# Sitara_DDR.net
KiCad netlist of a schematic drawn in Altium Designer
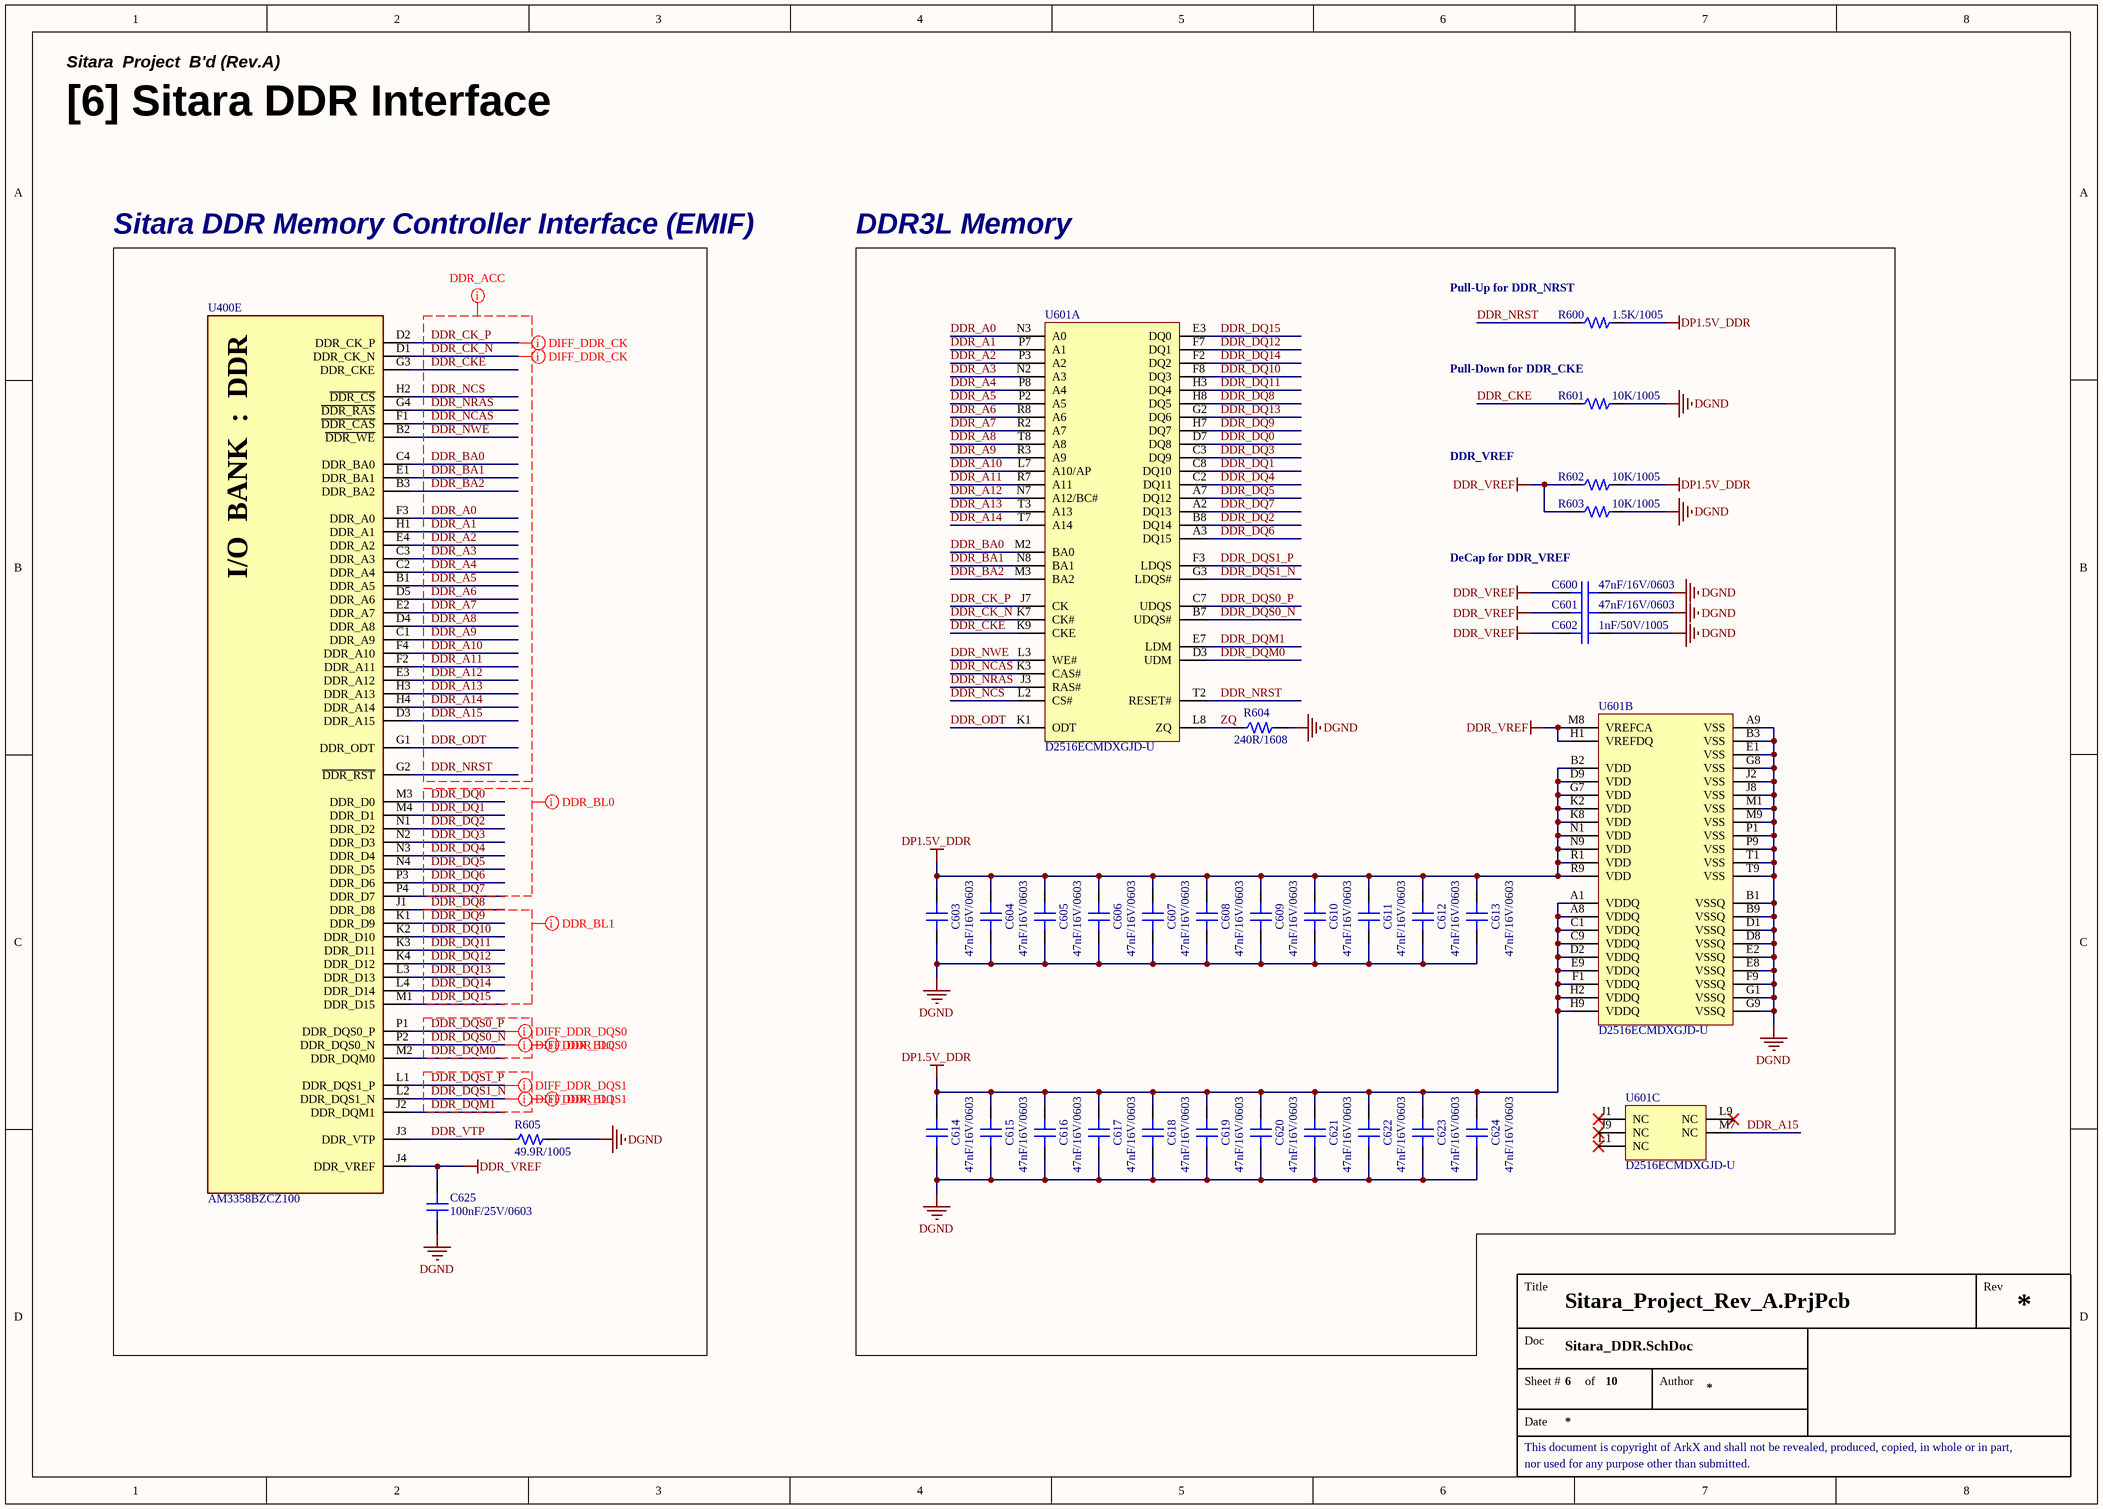
[diagram p0: Sitara_DDR.SchDoc]

(export (version "E")
  (design (tool "Eeschema 10.0.6"))
  (components
    (comp (ref "C600")
      (value "47nF/16V/0603")
      (footprint "CAP 0603 (0201_INCH)")
      (description "16V 47nF X5R ±10% 0201 Multilayer Ceramic Capacitors MLCC - SMD/SMT ROHS")
      (fields (field (name "LCSC PART #") "C88917"))
      (libsource (lib "Arkx") (part "CAP_47nF/16V/0603"))
    )
    (comp (ref "C601")
      (value "47nF/16V/0603")
      (footprint "CAP 0603 (0201_INCH)")
      (description "16V 47nF X5R ±10% 0201 Multilayer Ceramic Capacitors MLCC - SMD/SMT ROHS")
      (fields (field (name "LCSC PART #") "C88917"))
      (libsource (lib "Arkx") (part "CAP_47nF/16V/0603"))
    )
    (comp (ref "C602")
      (value "1nF/50V/1005")
      (footprint "CAP 1005 (0402_INCH)")
      (description "Ceramic CAP_1nF/50V/1005")
      (fields (field (name "LCSC PART #") "C1523"))
      (libsource (lib "Arkx") (part "CAP_1nF/50V/1005"))
    )
    (comp (ref "C603")
      (value "47nF/16V/0603")
      (footprint "CAP 0603 (0201_INCH)")
      (description "16V 47nF X5R ±10% 0201 Multilayer Ceramic Capacitors MLCC - SMD/SMT ROHS")
      (fields (field (name "LCSC PART #") "C88917"))
      (libsource (lib "Arkx") (part "CAP_47nF/16V/0603"))
    )
    (comp (ref "C604")
      (value "47nF/16V/0603")
      (footprint "CAP 0603 (0201_INCH)")
      (description "16V 47nF X5R ±10% 0201 Multilayer Ceramic Capacitors MLCC - SMD/SMT ROHS")
      (fields (field (name "LCSC PART #") "C88917"))
      (libsource (lib "Arkx") (part "CAP_47nF/16V/0603"))
    )
    (comp (ref "C605")
      (value "47nF/16V/0603")
      (footprint "CAP 0603 (0201_INCH)")
      (description "16V 47nF X5R ±10% 0201 Multilayer Ceramic Capacitors MLCC - SMD/SMT ROHS")
      (fields (field (name "LCSC PART #") "C88917"))
      (libsource (lib "Arkx") (part "CAP_47nF/16V/0603"))
    )
    (comp (ref "C606")
      (value "47nF/16V/0603")
      (footprint "CAP 0603 (0201_INCH)")
      (description "16V 47nF X5R ±10% 0201 Multilayer Ceramic Capacitors MLCC - SMD/SMT ROHS")
      (fields (field (name "LCSC PART #") "C88917"))
      (libsource (lib "Arkx") (part "CAP_47nF/16V/0603"))
    )
    (comp (ref "C607")
      (value "47nF/16V/0603")
      (footprint "CAP 0603 (0201_INCH)")
      (description "16V 47nF X5R ±10% 0201 Multilayer Ceramic Capacitors MLCC - SMD/SMT ROHS")
      (fields (field (name "LCSC PART #") "C88917"))
      (libsource (lib "Arkx") (part "CAP_47nF/16V/0603"))
    )
    (comp (ref "C608")
      (value "47nF/16V/0603")
      (footprint "CAP 0603 (0201_INCH)")
      (description "16V 47nF X5R ±10% 0201 Multilayer Ceramic Capacitors MLCC - SMD/SMT ROHS")
      (fields (field (name "LCSC PART #") "C88917"))
      (libsource (lib "Arkx") (part "CAP_47nF/16V/0603"))
    )
    (comp (ref "C609")
      (value "47nF/16V/0603")
      (footprint "CAP 0603 (0201_INCH)")
      (description "16V 47nF X5R ±10% 0201 Multilayer Ceramic Capacitors MLCC - SMD/SMT ROHS")
      (fields (field (name "LCSC PART #") "C88917"))
      (libsource (lib "Arkx") (part "CAP_47nF/16V/0603"))
    )
    (comp (ref "C610")
      (value "47nF/16V/0603")
      (footprint "CAP 0603 (0201_INCH)")
      (description "16V 47nF X5R ±10% 0201 Multilayer Ceramic Capacitors MLCC - SMD/SMT ROHS")
      (fields (field (name "LCSC PART #") "C88917"))
      (libsource (lib "Arkx") (part "CAP_47nF/16V/0603"))
    )
    (comp (ref "C611")
      (value "47nF/16V/0603")
      (footprint "CAP 0603 (0201_INCH)")
      (description "16V 47nF X5R ±10% 0201 Multilayer Ceramic Capacitors MLCC - SMD/SMT ROHS")
      (fields (field (name "LCSC PART #") "C88917"))
      (libsource (lib "Arkx") (part "CAP_47nF/16V/0603"))
    )
    (comp (ref "C612")
      (value "47nF/16V/0603")
      (footprint "CAP 0603 (0201_INCH)")
      (description "16V 47nF X5R ±10% 0201 Multilayer Ceramic Capacitors MLCC - SMD/SMT ROHS")
      (fields (field (name "LCSC PART #") "C88917"))
      (libsource (lib "Arkx") (part "CAP_47nF/16V/0603"))
    )
    (comp (ref "C613")
      (value "47nF/16V/0603")
      (footprint "CAP 0603 (0201_INCH)")
      (description "16V 47nF X5R ±10% 0201 Multilayer Ceramic Capacitors MLCC - SMD/SMT ROHS")
      (fields (field (name "LCSC PART #") "C88917"))
      (libsource (lib "Arkx") (part "CAP_47nF/16V/0603"))
    )
    (comp (ref "C614")
      (value "47nF/16V/0603")
      (footprint "CAP 0603 (0201_INCH)")
      (description "16V 47nF X5R ±10% 0201 Multilayer Ceramic Capacitors MLCC - SMD/SMT ROHS")
      (fields (field (name "LCSC PART #") "C88917"))
      (libsource (lib "Arkx") (part "CAP_47nF/16V/0603"))
    )
    (comp (ref "C615")
      (value "47nF/16V/0603")
      (footprint "CAP 0603 (0201_INCH)")
      (description "16V 47nF X5R ±10% 0201 Multilayer Ceramic Capacitors MLCC - SMD/SMT ROHS")
      (fields (field (name "LCSC PART #") "C88917"))
      (libsource (lib "Arkx") (part "CAP_47nF/16V/0603"))
    )
    (comp (ref "C616")
      (value "47nF/16V/0603")
      (footprint "CAP 0603 (0201_INCH)")
      (description "16V 47nF X5R ±10% 0201 Multilayer Ceramic Capacitors MLCC - SMD/SMT ROHS")
      (fields (field (name "LCSC PART #") "C88917"))
      (libsource (lib "Arkx") (part "CAP_47nF/16V/0603"))
    )
    (comp (ref "C617")
      (value "47nF/16V/0603")
      (footprint "CAP 0603 (0201_INCH)")
      (description "16V 47nF X5R ±10% 0201 Multilayer Ceramic Capacitors MLCC - SMD/SMT ROHS")
      (fields (field (name "LCSC PART #") "C88917"))
      (libsource (lib "Arkx") (part "CAP_47nF/16V/0603"))
    )
    (comp (ref "C618")
      (value "47nF/16V/0603")
      (footprint "CAP 0603 (0201_INCH)")
      (description "16V 47nF X5R ±10% 0201 Multilayer Ceramic Capacitors MLCC - SMD/SMT ROHS")
      (fields (field (name "LCSC PART #") "C88917"))
      (libsource (lib "Arkx") (part "CAP_47nF/16V/0603"))
    )
    (comp (ref "C619")
      (value "47nF/16V/0603")
      (footprint "CAP 0603 (0201_INCH)")
      (description "16V 47nF X5R ±10% 0201 Multilayer Ceramic Capacitors MLCC - SMD/SMT ROHS")
      (fields (field (name "LCSC PART #") "C88917"))
      (libsource (lib "Arkx") (part "CAP_47nF/16V/0603"))
    )
    (comp (ref "C620")
      (value "47nF/16V/0603")
      (footprint "CAP 0603 (0201_INCH)")
      (description "16V 47nF X5R ±10% 0201 Multilayer Ceramic Capacitors MLCC - SMD/SMT ROHS")
      (fields (field (name "LCSC PART #") "C88917"))
      (libsource (lib "Arkx") (part "CAP_47nF/16V/0603"))
    )
    (comp (ref "C621")
      (value "47nF/16V/0603")
      (footprint "CAP 0603 (0201_INCH)")
      (description "16V 47nF X5R ±10% 0201 Multilayer Ceramic Capacitors MLCC - SMD/SMT ROHS")
      (fields (field (name "LCSC PART #") "C88917"))
      (libsource (lib "Arkx") (part "CAP_47nF/16V/0603"))
    )
    (comp (ref "C622")
      (value "47nF/16V/0603")
      (footprint "CAP 0603 (0201_INCH)")
      (description "16V 47nF X5R ±10% 0201 Multilayer Ceramic Capacitors MLCC - SMD/SMT ROHS")
      (fields (field (name "LCSC PART #") "C88917"))
      (libsource (lib "Arkx") (part "CAP_47nF/16V/0603"))
    )
    (comp (ref "C623")
      (value "47nF/16V/0603")
      (footprint "CAP 0603 (0201_INCH)")
      (description "16V 47nF X5R ±10% 0201 Multilayer Ceramic Capacitors MLCC - SMD/SMT ROHS")
      (fields (field (name "LCSC PART #") "C88917"))
      (libsource (lib "Arkx") (part "CAP_47nF/16V/0603"))
    )
    (comp (ref "C624")
      (value "47nF/16V/0603")
      (footprint "CAP 0603 (0201_INCH)")
      (description "16V 47nF X5R ±10% 0201 Multilayer Ceramic Capacitors MLCC - SMD/SMT ROHS")
      (fields (field (name "LCSC PART #") "C88917"))
      (libsource (lib "Arkx") (part "CAP_47nF/16V/0603"))
    )
    (comp (ref "C625")
      (value "100nF/25V/0603")
      (footprint "CAP 0603 (0201_INCH)")
      (description "Ceramic CAP_100nF/25V/0603")
      (fields (field (name "LCSC PART #") "C181047"))
      (libsource (lib "Arkx") (part "CAP_100nF/25V/0603"))
    )
    (comp (ref "R600")
      (value "1.5K/1005")
      (footprint "RES 1005 (0402_inch)")
      (description "RES_1.5K/1005/62.5mW")
      (fields (field (name "LCSC PART #") "C25867"))
      (libsource (lib "Arkx") (part "RES_1.5K/1005/62.5mW"))
    )
    (comp (ref "R601")
      (value "10K/1005")
      (footprint "RES 1005 (0402_inch)")
      (description "RES_10K/1005/62.5mW")
      (fields (field (name "LCSC PART #") "C25744"))
      (libsource (lib "Arkx") (part "RES_10K/1005/62.5mW"))
    )
    (comp (ref "R602")
      (value "10K/1005")
      (footprint "RES 1005 (0402_inch)")
      (description "RES_10K/1005/62.5mW")
      (fields (field (name "LCSC PART #") "C25744"))
      (libsource (lib "Arkx") (part "RES_10K/1005/62.5mW"))
    )
    (comp (ref "R603")
      (value "10K/1005")
      (footprint "RES 1005 (0402_inch)")
      (description "RES_10K/1005/62.5mW")
      (fields (field (name "LCSC PART #") "C25744"))
      (libsource (lib "Arkx") (part "RES_10K/1005/62.5mW"))
    )
    (comp (ref "R604")
      (value "240R/1608")
      (footprint "RES 1608 (0603_inch)")
      (description "RES_240R/1608/0.1W")
      (fields (field (name "LCSC PART #") "C23350"))
      (libsource (lib "Arkx") (part "RES_240R/1608/0.1W"))
    )
    (comp (ref "R605")
      (value "49.9R/1005")
      (footprint "RES 1005 (0402_inch)")
      (description "RES_49.9R/1005/62.5mW")
      (fields (field (name "LCSC PART #") "C25120"))
      (libsource (lib "Arkx") (part "RES_49.9R/1005/62.5mW"))
    )
    (comp (ref "U400")
      (value "AM3358BZCZ100")
      (footprint "IC_SOC_AM3358BZCZ100")
      (description "ARM® Cortex®-A8 Microprocessor IC Sitara™ 1 Core, 32-Bit 1.0GHz 324-NFBGA (15x15)")
      (fields (field (name "LCSC PART #") "C73932"))
      (libsource (lib "Arkx") (part "IC_SOC_AM3358BZCZ100"))
    )
    (comp (ref "U601")
      (value "D2516ECMDXGJD-U")
      (footprint "IC_MEM_DDR3L_MT41K256M16TW-107 IT:P")
      (description "DRAM 4Gb 96 ball FBGA DDR3L 1866")
      (fields (field (name "LCSC PART #") "C2927180"))
      (libsource (lib "Arkx") (part "IC_MEM_DDR3L_D2516ECMDXGJD-U"))
    )
  )
  (nets
    (net (code "1") (name "/DDR_A0") (class "Default")
      (node (ref "U400") (pin "F3") (pinfunction "DDR_A0_F3") (pintype "passive"))
      (node (ref "U601") (pin "N3") (pinfunction "A0_N3") (pintype "passive"))
    )
    (net (code "2") (name "/DDR_A1") (class "Default")
      (node (ref "U400") (pin "H1") (pinfunction "DDR_A1_H1") (pintype "passive"))
      (node (ref "U601") (pin "P7") (pinfunction "A1_P7") (pintype "passive"))
    )
    (net (code "3") (name "/DDR_A2") (class "Default")
      (node (ref "U400") (pin "E4") (pinfunction "DDR_A2_E4") (pintype "passive"))
      (node (ref "U601") (pin "P3") (pinfunction "A2_P3") (pintype "passive"))
    )
    (net (code "4") (name "/DDR_A3") (class "Default")
      (node (ref "U400") (pin "C3") (pinfunction "DDR_A3_C3") (pintype "passive"))
      (node (ref "U601") (pin "N2") (pinfunction "A3_N2") (pintype "passive"))
    )
    (net (code "5") (name "/DDR_A4") (class "Default")
      (node (ref "U400") (pin "C2") (pinfunction "DDR_A4_C2") (pintype "passive"))
      (node (ref "U601") (pin "P8") (pinfunction "A4_P8") (pintype "passive"))
    )
    (net (code "6") (name "/DDR_A5") (class "Default")
      (node (ref "U400") (pin "B1") (pinfunction "DDR_A5_B1") (pintype "passive"))
      (node (ref "U601") (pin "P2") (pinfunction "A5_P2") (pintype "passive"))
    )
    (net (code "7") (name "/DDR_A6") (class "Default")
      (node (ref "U400") (pin "D5") (pinfunction "DDR_A6_D5") (pintype "passive"))
      (node (ref "U601") (pin "R8") (pinfunction "A6_R8") (pintype "passive"))
    )
    (net (code "8") (name "/DDR_A7") (class "Default")
      (node (ref "U400") (pin "E2") (pinfunction "DDR_A7_E2") (pintype "passive"))
      (node (ref "U601") (pin "R2") (pinfunction "A7_R2") (pintype "passive"))
    )
    (net (code "9") (name "/DDR_A8") (class "Default")
      (node (ref "U400") (pin "D4") (pinfunction "DDR_A8_D4") (pintype "passive"))
      (node (ref "U601") (pin "T8") (pinfunction "A8_T8") (pintype "passive"))
    )
    (net (code "10") (name "/DDR_A9") (class "Default")
      (node (ref "U400") (pin "C1") (pinfunction "DDR_A9_C1") (pintype "passive"))
      (node (ref "U601") (pin "R3") (pinfunction "A9_R3") (pintype "passive"))
    )
    (net (code "11") (name "/DDR_A10") (class "Default")
      (node (ref "U400") (pin "F4") (pinfunction "DDR_A10_F4") (pintype "passive"))
      (node (ref "U601") (pin "L7") (pinfunction "A10/AP_L7") (pintype "passive"))
    )
    (net (code "12") (name "/DDR_A11") (class "Default")
      (node (ref "U400") (pin "F2") (pinfunction "DDR_A11_F2") (pintype "passive"))
      (node (ref "U601") (pin "R7") (pinfunction "A11_R7") (pintype "passive"))
    )
    (net (code "13") (name "/DDR_A12") (class "Default")
      (node (ref "U400") (pin "E3") (pinfunction "DDR_A12_E3") (pintype "passive"))
      (node (ref "U601") (pin "N7") (pinfunction "A12/BC#_N7") (pintype "passive"))
    )
    (net (code "14") (name "/DDR_A13") (class "Default")
      (node (ref "U400") (pin "H3") (pinfunction "DDR_A13_H3") (pintype "passive"))
      (node (ref "U601") (pin "T3") (pinfunction "A13_T3") (pintype "passive"))
    )
    (net (code "15") (name "/DDR_A14") (class "Default")
      (node (ref "U400") (pin "H4") (pinfunction "DDR_A14_H4") (pintype "passive"))
      (node (ref "U601") (pin "T7") (pinfunction "A14_T7") (pintype "passive"))
    )
    (net (code "16") (name "/DDR_A15") (class "Default")
      (node (ref "U400") (pin "D3") (pinfunction "DDR_A15_D3") (pintype "passive"))
      (node (ref "U601") (pin "M7") (pinfunction "NC_M7") (pintype "passive"))
    )
    (net (code "17") (name "/DDR_BA0") (class "Default")
      (node (ref "U400") (pin "C4") (pinfunction "DDR_BA0_C4") (pintype "passive"))
      (node (ref "U601") (pin "M2") (pinfunction "BA0_M2") (pintype "passive"))
    )
    (net (code "18") (name "/DDR_BA1") (class "Default")
      (node (ref "U400") (pin "E1") (pinfunction "DDR_BA1_E1") (pintype "passive"))
      (node (ref "U601") (pin "N8") (pinfunction "BA1_N8") (pintype "passive"))
    )
    (net (code "19") (name "/DDR_BA2") (class "Default")
      (node (ref "U400") (pin "B3") (pinfunction "DDR_BA2_B3") (pintype "passive"))
      (node (ref "U601") (pin "M3") (pinfunction "BA2_M3") (pintype "passive"))
    )
    (net (code "20") (name "/DDR_CKE") (class "Default")
      (node (ref "R601") (pin "1") (pinfunction "1_1") (pintype "passive"))
      (node (ref "U400") (pin "G3") (pinfunction "DDR_CKE_G3") (pintype "passive"))
      (node (ref "U601") (pin "K9") (pinfunction "CKE_K9") (pintype "passive"))
    )
    (net (code "21") (name "/DDR_CK_N") (class "Default")
      (node (ref "U400") (pin "D1") (pinfunction "DDR_CK_N_D1") (pintype "passive"))
      (node (ref "U601") (pin "K7") (pinfunction "CK#_K7") (pintype "passive"))
    )
    (net (code "22") (name "/DDR_CK_P") (class "Default")
      (node (ref "U400") (pin "D2") (pinfunction "DDR_CK_P_D2") (pintype "passive"))
      (node (ref "U601") (pin "J7") (pinfunction "CK_J7") (pintype "passive"))
    )
    (net (code "23") (name "/DDR_DQ0") (class "Default")
      (node (ref "U400") (pin "M3") (pinfunction "DDR_D0_M3") (pintype "passive"))
      (node (ref "U601") (pin "D7") (pinfunction "DQ8_D7") (pintype "passive"))
    )
    (net (code "24") (name "/DDR_DQ1") (class "Default")
      (node (ref "U400") (pin "M4") (pinfunction "DDR_D1_M4") (pintype "passive"))
      (node (ref "U601") (pin "C8") (pinfunction "DQ10_C8") (pintype "passive"))
    )
    (net (code "25") (name "/DDR_DQ2") (class "Default")
      (node (ref "U400") (pin "N1") (pinfunction "DDR_D2_N1") (pintype "passive"))
      (node (ref "U601") (pin "B8") (pinfunction "DQ14_B8") (pintype "passive"))
    )
    (net (code "26") (name "/DDR_DQ3") (class "Default")
      (node (ref "U400") (pin "N2") (pinfunction "DDR_D3_N2") (pintype "passive"))
      (node (ref "U601") (pin "C3") (pinfunction "DQ9_C3") (pintype "passive"))
    )
    (net (code "27") (name "/DDR_DQ4") (class "Default")
      (node (ref "U400") (pin "N3") (pinfunction "DDR_D4_N3") (pintype "passive"))
      (node (ref "U601") (pin "C2") (pinfunction "DQ11_C2") (pintype "passive"))
    )
    (net (code "28") (name "/DDR_DQ5") (class "Default")
      (node (ref "U400") (pin "N4") (pinfunction "DDR_D5_N4") (pintype "passive"))
      (node (ref "U601") (pin "A7") (pinfunction "DQ12_A7") (pintype "passive"))
    )
    (net (code "29") (name "/DDR_DQ6") (class "Default")
      (node (ref "U400") (pin "P3") (pinfunction "DDR_D6_P3") (pintype "passive"))
      (node (ref "U601") (pin "A3") (pinfunction "DQ15_A3") (pintype "passive"))
    )
    (net (code "30") (name "/DDR_DQ7") (class "Default")
      (node (ref "U400") (pin "P4") (pinfunction "DDR_D7_P4") (pintype "passive"))
      (node (ref "U601") (pin "A2") (pinfunction "DQ13_A2") (pintype "passive"))
    )
    (net (code "31") (name "/DDR_DQ8") (class "Default")
      (node (ref "U400") (pin "J1") (pinfunction "DDR_D8_J1") (pintype "passive"))
      (node (ref "U601") (pin "H8") (pinfunction "DQ5_H8") (pintype "passive"))
    )
    (net (code "32") (name "/DDR_DQ9") (class "Default")
      (node (ref "U400") (pin "K1") (pinfunction "DDR_D9_K1") (pintype "passive"))
      (node (ref "U601") (pin "H7") (pinfunction "DQ7_H7") (pintype "passive"))
    )
    (net (code "33") (name "/DDR_DQ10") (class "Default")
      (node (ref "U400") (pin "K2") (pinfunction "DDR_D10_K2") (pintype "passive"))
      (node (ref "U601") (pin "F8") (pinfunction "DQ3_F8") (pintype "passive"))
    )
    (net (code "34") (name "/DDR_DQ11") (class "Default")
      (node (ref "U400") (pin "K3") (pinfunction "DDR_D11_K3") (pintype "passive"))
      (node (ref "U601") (pin "H3") (pinfunction "DQ4_H3") (pintype "passive"))
    )
    (net (code "35") (name "/DDR_DQ12") (class "Default")
      (node (ref "U400") (pin "K4") (pinfunction "DDR_D12_K4") (pintype "passive"))
      (node (ref "U601") (pin "F7") (pinfunction "DQ1_F7") (pintype "passive"))
    )
    (net (code "36") (name "/DDR_DQ13") (class "Default")
      (node (ref "U400") (pin "L3") (pinfunction "DDR_D13_L3") (pintype "passive"))
      (node (ref "U601") (pin "G2") (pinfunction "DQ6_G2") (pintype "passive"))
    )
    (net (code "37") (name "/DDR_DQ14") (class "Default")
      (node (ref "U400") (pin "L4") (pinfunction "DDR_D14_L4") (pintype "passive"))
      (node (ref "U601") (pin "F2") (pinfunction "DQ2_F2") (pintype "passive"))
    )
    (net (code "38") (name "/DDR_DQ15") (class "Default")
      (node (ref "U400") (pin "M1") (pinfunction "DDR_D15_M1") (pintype "passive"))
      (node (ref "U601") (pin "E3") (pinfunction "DQ0_E3") (pintype "passive"))
    )
    (net (code "39") (name "/DDR_DQM0") (class "Default")
      (node (ref "U400") (pin "M2") (pinfunction "DDR_DQM0_M2") (pintype "passive"))
      (node (ref "U601") (pin "D3") (pinfunction "UDM_D3") (pintype "passive"))
    )
    (net (code "40") (name "/DDR_DQM1") (class "Default")
      (node (ref "U400") (pin "J2") (pinfunction "DDR_DQM1_J2") (pintype "passive"))
      (node (ref "U601") (pin "E7") (pinfunction "LDM_E7") (pintype "passive"))
    )
    (net (code "41") (name "/DDR_DQS0_N") (class "Default")
      (node (ref "U400") (pin "P2") (pinfunction "DDR_DQS0_N_P2") (pintype "passive"))
      (node (ref "U601") (pin "B7") (pinfunction "UDQS#_B7") (pintype "passive"))
    )
    (net (code "42") (name "/DDR_DQS0_P") (class "Default")
      (node (ref "U400") (pin "P1") (pinfunction "DDR_DQS0_P_P1") (pintype "passive"))
      (node (ref "U601") (pin "C7") (pinfunction "UDQS_C7") (pintype "passive"))
    )
    (net (code "43") (name "/DDR_DQS1_N") (class "Default")
      (node (ref "U400") (pin "L2") (pinfunction "DDR_DQS1_N_L2") (pintype "passive"))
      (node (ref "U601") (pin "G3") (pinfunction "LDQS#_G3") (pintype "passive"))
    )
    (net (code "44") (name "/DDR_DQS1_P") (class "Default")
      (node (ref "U400") (pin "L1") (pinfunction "DDR_DQS1_P_L1") (pintype "passive"))
      (node (ref "U601") (pin "F3") (pinfunction "LDQS_F3") (pintype "passive"))
    )
    (net (code "45") (name "/DDR_NCAS") (class "Default")
      (node (ref "U400") (pin "F1") (pinfunction "~{DDR_CAS}_F1") (pintype "passive"))
      (node (ref "U601") (pin "K3") (pinfunction "CAS#_K3") (pintype "passive"))
    )
    (net (code "46") (name "/DDR_NCS") (class "Default")
      (node (ref "U400") (pin "H2") (pinfunction "~{DDR_CS}_H2") (pintype "passive"))
      (node (ref "U601") (pin "L2") (pinfunction "CS#_L2") (pintype "passive"))
    )
    (net (code "47") (name "/DDR_NRAS") (class "Default")
      (node (ref "U400") (pin "G4") (pinfunction "~{DDR_RAS}_G4") (pintype "passive"))
      (node (ref "U601") (pin "J3") (pinfunction "RAS#_J3") (pintype "passive"))
    )
    (net (code "48") (name "/DDR_NRST") (class "Default")
      (node (ref "R600") (pin "1") (pinfunction "1_1") (pintype "passive"))
      (node (ref "U400") (pin "G2") (pinfunction "~{DDR_RST}_G2") (pintype "passive"))
      (node (ref "U601") (pin "T2") (pinfunction "RESET#_T2") (pintype "passive"))
    )
    (net (code "49") (name "/DDR_NWE") (class "Default")
      (node (ref "U400") (pin "B2") (pinfunction "~{DDR_WE}_B2") (pintype "passive"))
      (node (ref "U601") (pin "L3") (pinfunction "WE#_L3") (pintype "passive"))
    )
    (net (code "50") (name "/DDR_ODT") (class "Default")
      (node (ref "U400") (pin "G1") (pinfunction "DDR_ODT_G1") (pintype "passive"))
      (node (ref "U601") (pin "K1") (pinfunction "ODT_K1") (pintype "passive"))
    )
    (net (code "51") (name "/DDR_VTP") (class "Default")
      (node (ref "R605") (pin "1") (pinfunction "1_1") (pintype "passive"))
      (node (ref "U400") (pin "J3") (pinfunction "DDR_VTP_J3") (pintype "passive"))
    )
    (net (code "52") (name "/ZQ") (class "Default")
      (node (ref "R604") (pin "1") (pinfunction "1_1") (pintype "passive"))
      (node (ref "U601") (pin "L8") (pinfunction "ZQ_L8") (pintype "passive"))
    )
    (net (code "53") (name "DDR_VREF") (class "Default")
      (node (ref "C600") (pin "1") (pinfunction "1_1") (pintype "passive"))
      (node (ref "C601") (pin "1") (pinfunction "1_1") (pintype "passive"))
      (node (ref "C602") (pin "1") (pinfunction "1_1") (pintype "passive"))
      (node (ref "C625") (pin "2") (pinfunction "2_2") (pintype "passive"))
      (node (ref "R602") (pin "1") (pinfunction "1_1") (pintype "passive"))
      (node (ref "R603") (pin "1") (pinfunction "1_1") (pintype "passive"))
      (node (ref "U400") (pin "J4") (pinfunction "DDR_VREF_J4") (pintype "passive"))
      (node (ref "U601") (pin "H1") (pinfunction "VREFDQ_H1") (pintype "passive"))
      (node (ref "U601") (pin "M8") (pinfunction "VREFCA_M8") (pintype "passive"))
    )
    (net (code "54") (name "DGND") (class "Default")
      (node (ref "C600") (pin "2") (pinfunction "2_2") (pintype "passive"))
      (node (ref "C601") (pin "2") (pinfunction "2_2") (pintype "passive"))
      (node (ref "C602") (pin "2") (pinfunction "2_2") (pintype "passive"))
      (node (ref "C603") (pin "1") (pinfunction "1_1") (pintype "passive"))
      (node (ref "C604") (pin "1") (pinfunction "1_1") (pintype "passive"))
      (node (ref "C605") (pin "1") (pinfunction "1_1") (pintype "passive"))
      (node (ref "C606") (pin "1") (pinfunction "1_1") (pintype "passive"))
      (node (ref "C607") (pin "1") (pinfunction "1_1") (pintype "passive"))
      (node (ref "C608") (pin "1") (pinfunction "1_1") (pintype "passive"))
      (node (ref "C609") (pin "1") (pinfunction "1_1") (pintype "passive"))
      (node (ref "C610") (pin "1") (pinfunction "1_1") (pintype "passive"))
      (node (ref "C611") (pin "1") (pinfunction "1_1") (pintype "passive"))
      (node (ref "C612") (pin "1") (pinfunction "1_1") (pintype "passive"))
      (node (ref "C613") (pin "1") (pinfunction "1_1") (pintype "passive"))
      (node (ref "C614") (pin "1") (pinfunction "1_1") (pintype "passive"))
      (node (ref "C615") (pin "1") (pinfunction "1_1") (pintype "passive"))
      (node (ref "C616") (pin "1") (pinfunction "1_1") (pintype "passive"))
      (node (ref "C617") (pin "1") (pinfunction "1_1") (pintype "passive"))
      (node (ref "C618") (pin "1") (pinfunction "1_1") (pintype "passive"))
      (node (ref "C619") (pin "1") (pinfunction "1_1") (pintype "passive"))
      (node (ref "C620") (pin "1") (pinfunction "1_1") (pintype "passive"))
      (node (ref "C621") (pin "1") (pinfunction "1_1") (pintype "passive"))
      (node (ref "C622") (pin "1") (pinfunction "1_1") (pintype "passive"))
      (node (ref "C623") (pin "1") (pinfunction "1_1") (pintype "passive"))
      (node (ref "C624") (pin "1") (pinfunction "1_1") (pintype "passive"))
      (node (ref "C625") (pin "1") (pinfunction "1_1") (pintype "passive"))
      (node (ref "R601") (pin "2") (pinfunction "2_2") (pintype "passive"))
      (node (ref "R603") (pin "2") (pinfunction "2_2") (pintype "passive"))
      (node (ref "R604") (pin "2") (pinfunction "2_2") (pintype "passive"))
      (node (ref "R605") (pin "2") (pinfunction "2_2") (pintype "passive"))
      (node (ref "U601") (pin "A9") (pinfunction "VSS_A9") (pintype "passive"))
      (node (ref "U601") (pin "B1") (pinfunction "VSSQ_B1") (pintype "passive"))
      (node (ref "U601") (pin "B3") (pinfunction "VSS_B3") (pintype "passive"))
      (node (ref "U601") (pin "B9") (pinfunction "VSSQ_B9") (pintype "passive"))
      (node (ref "U601") (pin "D1") (pinfunction "VSSQ_D1") (pintype "passive"))
      (node (ref "U601") (pin "D8") (pinfunction "VSSQ_D8") (pintype "passive"))
      (node (ref "U601") (pin "E1") (pinfunction "VSS_E1") (pintype "passive"))
      (node (ref "U601") (pin "E2") (pinfunction "VSSQ_E2") (pintype "passive"))
      (node (ref "U601") (pin "E8") (pinfunction "VSSQ_E8") (pintype "passive"))
      (node (ref "U601") (pin "F9") (pinfunction "VSSQ_F9") (pintype "passive"))
      (node (ref "U601") (pin "G1") (pinfunction "VSSQ_G1") (pintype "passive"))
      (node (ref "U601") (pin "G8") (pinfunction "VSS_G8") (pintype "passive"))
      (node (ref "U601") (pin "G9") (pinfunction "VSSQ_G9") (pintype "passive"))
      (node (ref "U601") (pin "J2") (pinfunction "VSS_J2") (pintype "passive"))
      (node (ref "U601") (pin "J8") (pinfunction "VSS_J8") (pintype "passive"))
      (node (ref "U601") (pin "M1") (pinfunction "VSS_M1") (pintype "passive"))
      (node (ref "U601") (pin "M9") (pinfunction "VSS_M9") (pintype "passive"))
      (node (ref "U601") (pin "P1") (pinfunction "VSS_P1") (pintype "passive"))
      (node (ref "U601") (pin "P9") (pinfunction "VSS_P9") (pintype "passive"))
      (node (ref "U601") (pin "T1") (pinfunction "VSS_T1") (pintype "passive"))
      (node (ref "U601") (pin "T9") (pinfunction "VSS_T9") (pintype "passive"))
    )
    (net (code "55") (name "DP1.5V_DDR") (class "Default")
      (node (ref "C603") (pin "2") (pinfunction "2_2") (pintype "passive"))
      (node (ref "C604") (pin "2") (pinfunction "2_2") (pintype "passive"))
      (node (ref "C605") (pin "2") (pinfunction "2_2") (pintype "passive"))
      (node (ref "C606") (pin "2") (pinfunction "2_2") (pintype "passive"))
      (node (ref "C607") (pin "2") (pinfunction "2_2") (pintype "passive"))
      (node (ref "C608") (pin "2") (pinfunction "2_2") (pintype "passive"))
      (node (ref "C609") (pin "2") (pinfunction "2_2") (pintype "passive"))
      (node (ref "C610") (pin "2") (pinfunction "2_2") (pintype "passive"))
      (node (ref "C611") (pin "2") (pinfunction "2_2") (pintype "passive"))
      (node (ref "C612") (pin "2") (pinfunction "2_2") (pintype "passive"))
      (node (ref "C613") (pin "2") (pinfunction "2_2") (pintype "passive"))
      (node (ref "C614") (pin "2") (pinfunction "2_2") (pintype "passive"))
      (node (ref "C615") (pin "2") (pinfunction "2_2") (pintype "passive"))
      (node (ref "C616") (pin "2") (pinfunction "2_2") (pintype "passive"))
      (node (ref "C617") (pin "2") (pinfunction "2_2") (pintype "passive"))
      (node (ref "C618") (pin "2") (pinfunction "2_2") (pintype "passive"))
      (node (ref "C619") (pin "2") (pinfunction "2_2") (pintype "passive"))
      (node (ref "C620") (pin "2") (pinfunction "2_2") (pintype "passive"))
      (node (ref "C621") (pin "2") (pinfunction "2_2") (pintype "passive"))
      (node (ref "C622") (pin "2") (pinfunction "2_2") (pintype "passive"))
      (node (ref "C623") (pin "2") (pinfunction "2_2") (pintype "passive"))
      (node (ref "C624") (pin "2") (pinfunction "2_2") (pintype "passive"))
      (node (ref "R600") (pin "2") (pinfunction "2_2") (pintype "passive"))
      (node (ref "R602") (pin "2") (pinfunction "2_2") (pintype "passive"))
      (node (ref "U601") (pin "A1") (pinfunction "VDDQ_A1") (pintype "passive"))
      (node (ref "U601") (pin "A8") (pinfunction "VDDQ_A8") (pintype "passive"))
      (node (ref "U601") (pin "B2") (pinfunction "VDD_B2") (pintype "passive"))
      (node (ref "U601") (pin "C1") (pinfunction "VDDQ_C1") (pintype "passive"))
      (node (ref "U601") (pin "C9") (pinfunction "VDDQ_C9") (pintype "passive"))
      (node (ref "U601") (pin "D2") (pinfunction "VDDQ_D2") (pintype "passive"))
      (node (ref "U601") (pin "D9") (pinfunction "VDD_D9") (pintype "passive"))
      (node (ref "U601") (pin "E9") (pinfunction "VDDQ_E9") (pintype "passive"))
      (node (ref "U601") (pin "F1") (pinfunction "VDDQ_F1") (pintype "passive"))
      (node (ref "U601") (pin "G7") (pinfunction "VDD_G7") (pintype "passive"))
      (node (ref "U601") (pin "H2") (pinfunction "VDDQ_H2") (pintype "passive"))
      (node (ref "U601") (pin "H9") (pinfunction "VDDQ_H9") (pintype "passive"))
      (node (ref "U601") (pin "K2") (pinfunction "VDD_K2") (pintype "passive"))
      (node (ref "U601") (pin "K8") (pinfunction "VDD_K8") (pintype "passive"))
      (node (ref "U601") (pin "N1") (pinfunction "VDD_N1") (pintype "passive"))
      (node (ref "U601") (pin "N9") (pinfunction "VDD_N9") (pintype "passive"))
      (node (ref "U601") (pin "R1") (pinfunction "VDD_R1") (pintype "passive"))
      (node (ref "U601") (pin "R9") (pinfunction "VDD_R9") (pintype "passive"))
    )
    (net (code "56") (name "unconnected-(U601C-NC-PadJ1)") (class "Default")
      (node (ref "U601") (pin "J1") (pinfunction "NC_J1") (pintype "passive+no_connect"))
    )
    (net (code "57") (name "unconnected-(U601C-NC-PadJ9)") (class "Default")
      (node (ref "U601") (pin "J9") (pinfunction "NC_J9") (pintype "passive+no_connect"))
    )
    (net (code "58") (name "unconnected-(U601C-NC-PadL1)") (class "Default")
      (node (ref "U601") (pin "L1") (pinfunction "NC_L1") (pintype "passive+no_connect"))
    )
    (net (code "59") (name "unconnected-(U601C-NC-PadL9)") (class "Default")
      (node (ref "U601") (pin "L9") (pinfunction "NC_L9") (pintype "passive+no_connect"))
    )
  )
)
